# Active_rectifier.net
KiCad netlist of a schematic drawn in EAGLE
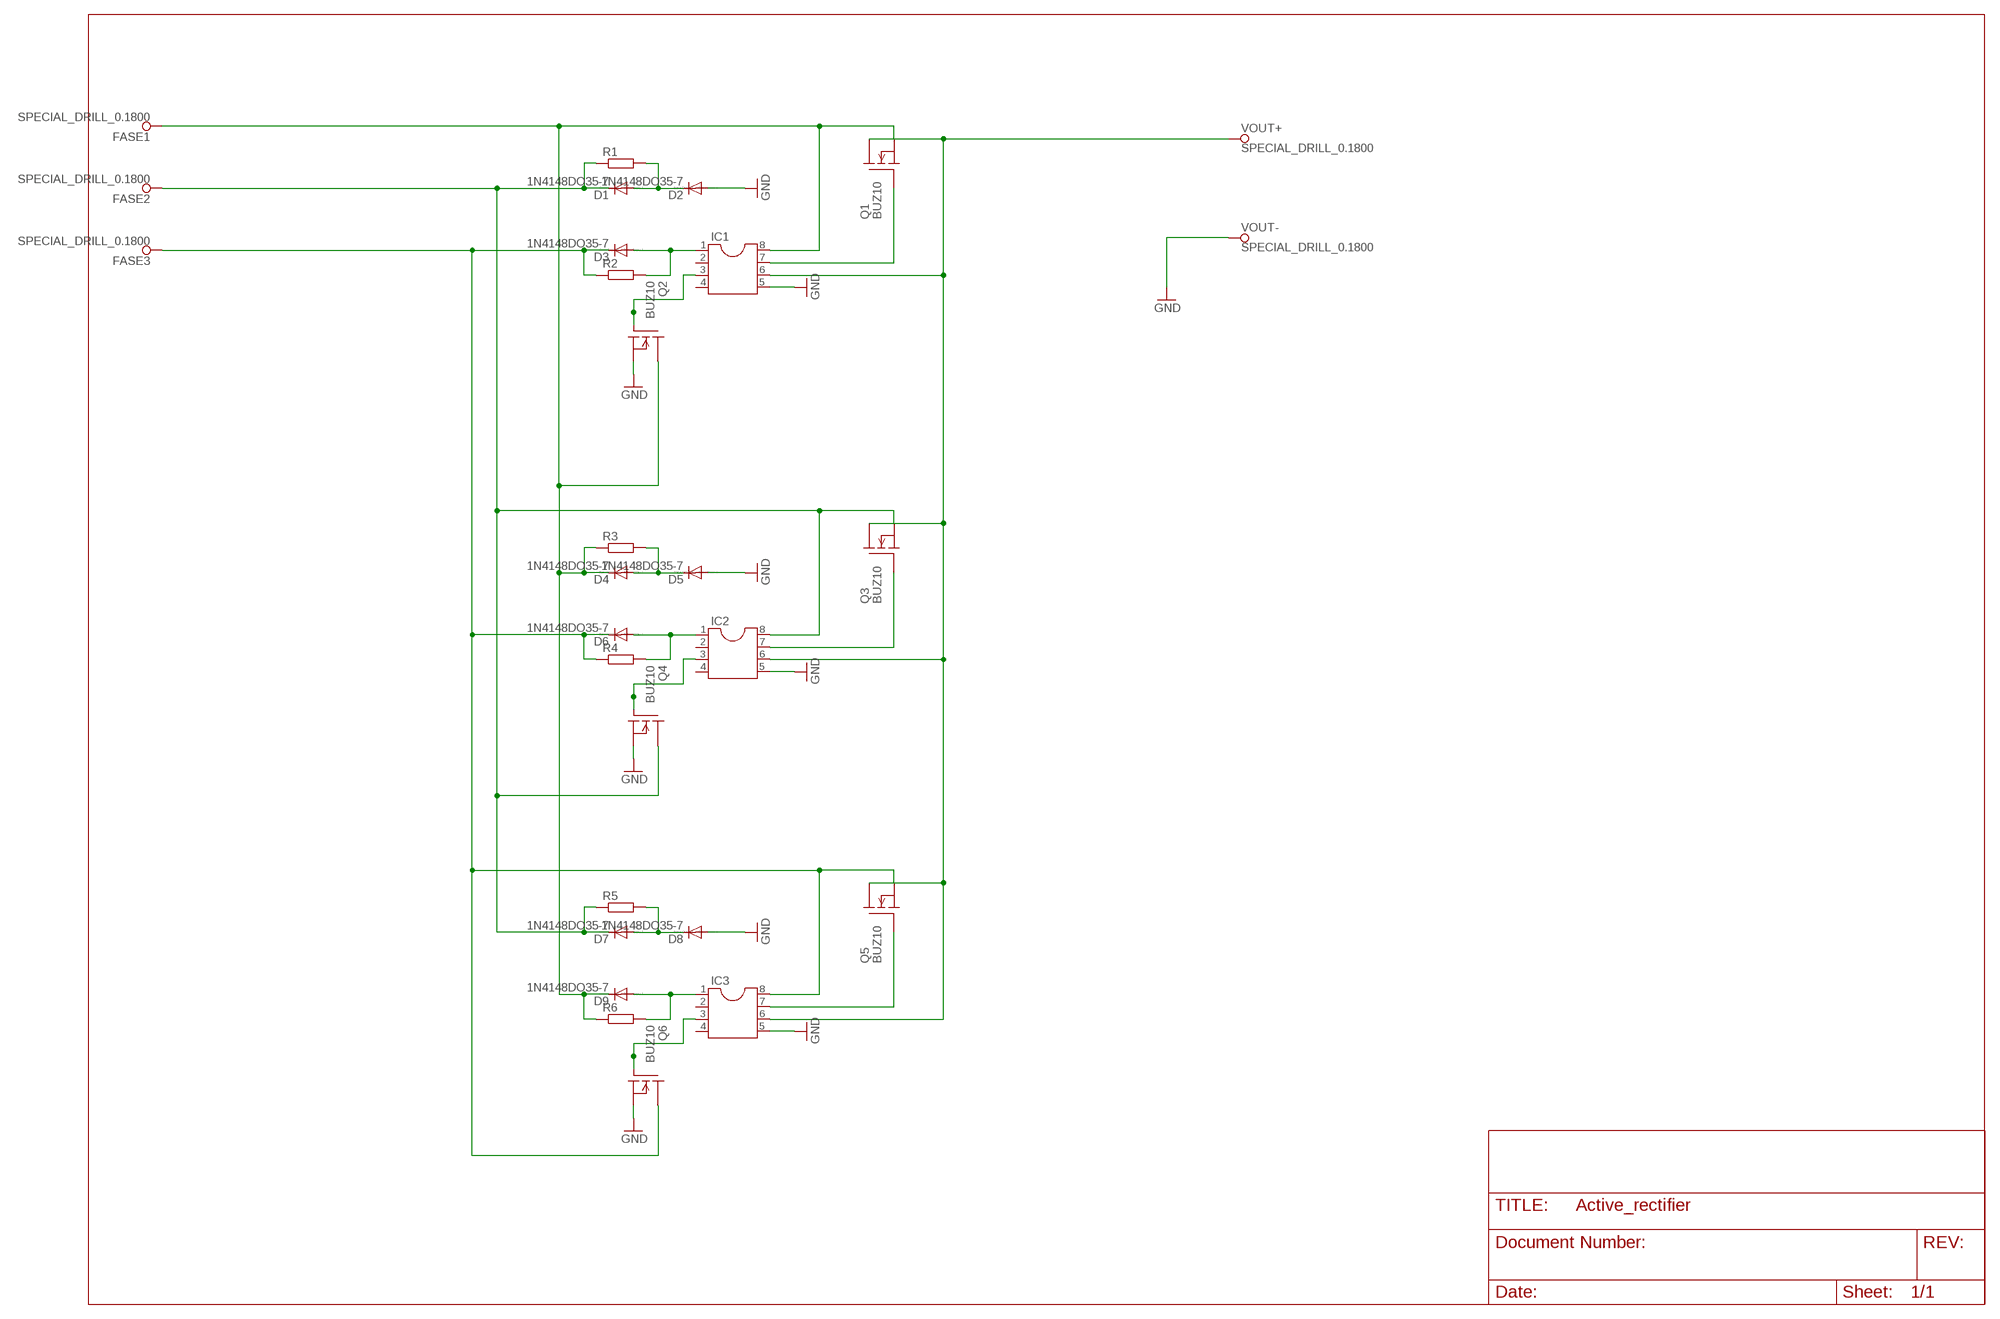
[diagram p0: schematic, sheet 1]

(export (version "E")
  (design (tool "Eeschema 10.0.6"))
  (components
    (comp (ref "D1")
      (value "1N4148DO35-7")
      (footprint "eagle-import:DO35-7")
      (libsource (lib "eagle-import") (part "1N4148DO35-7"))
    )
    (comp (ref "D2")
      (value "1N4148DO35-7")
      (footprint "eagle-import:DO35-7")
      (libsource (lib "eagle-import") (part "1N4148DO35-7"))
    )
    (comp (ref "D3")
      (value "1N4148DO35-7")
      (footprint "eagle-import:DO35-7")
      (libsource (lib "eagle-import") (part "1N4148DO35-7"))
    )
    (comp (ref "D4")
      (value "1N4148DO35-7")
      (footprint "eagle-import:DO35-7")
      (libsource (lib "eagle-import") (part "1N4148DO35-7"))
    )
    (comp (ref "D5")
      (value "1N4148DO35-7")
      (footprint "eagle-import:DO35-7")
      (libsource (lib "eagle-import") (part "1N4148DO35-7"))
    )
    (comp (ref "D6")
      (value "1N4148DO35-7")
      (footprint "eagle-import:DO35-7")
      (libsource (lib "eagle-import") (part "1N4148DO35-7"))
    )
    (comp (ref "D7")
      (value "1N4148DO35-7")
      (footprint "eagle-import:DO35-7")
      (libsource (lib "eagle-import") (part "1N4148DO35-7"))
    )
    (comp (ref "D8")
      (value "1N4148DO35-7")
      (footprint "eagle-import:DO35-7")
      (libsource (lib "eagle-import") (part "1N4148DO35-7"))
    )
    (comp (ref "D9")
      (value "1N4148DO35-7")
      (footprint "eagle-import:DO35-7")
      (libsource (lib "eagle-import") (part "1N4148DO35-7"))
    )
    (comp (ref "FASE1")
      (value "SPECIAL_DRILL_0.1800")
      (footprint "eagle-import:PAD_0.1800")
      (libsource (lib "eagle-import") (part "SPECIAL_DRILL_0.1800"))
    )
    (comp (ref "FASE2")
      (value "SPECIAL_DRILL_0.1800")
      (footprint "eagle-import:PAD_0.1800")
      (libsource (lib "eagle-import") (part "SPECIAL_DRILL_0.1800"))
    )
    (comp (ref "FASE3")
      (value "SPECIAL_DRILL_0.1800")
      (footprint "eagle-import:PAD_0.1800")
      (libsource (lib "eagle-import") (part "SPECIAL_DRILL_0.1800"))
    )
    (comp (ref "IC1")
      (value "DIL8")
      (footprint "eagle-import:DIL08")
      (libsource (lib "eagle-import") (part "DIL8"))
    )
    (comp (ref "IC2")
      (value "DIL8")
      (footprint "eagle-import:DIL08")
      (libsource (lib "eagle-import") (part "DIL8"))
    )
    (comp (ref "IC3")
      (value "DIL8")
      (footprint "eagle-import:DIL08")
      (libsource (lib "eagle-import") (part "DIL8"))
    )
    (comp (ref "Q1")
      (value "BUZ10")
      (footprint "eagle-import:TO220")
      (libsource (lib "eagle-import") (part "BUZ10"))
    )
    (comp (ref "Q2")
      (value "BUZ10")
      (footprint "eagle-import:TO220")
      (libsource (lib "eagle-import") (part "BUZ10"))
    )
    (comp (ref "Q3")
      (value "BUZ10")
      (footprint "eagle-import:TO220")
      (libsource (lib "eagle-import") (part "BUZ10"))
    )
    (comp (ref "Q4")
      (value "BUZ10")
      (footprint "eagle-import:TO220")
      (libsource (lib "eagle-import") (part "BUZ10"))
    )
    (comp (ref "Q5")
      (value "BUZ10")
      (footprint "eagle-import:TO220")
      (libsource (lib "eagle-import") (part "BUZ10"))
    )
    (comp (ref "Q6")
      (value "BUZ10")
      (footprint "eagle-import:TO220")
      (libsource (lib "eagle-import") (part "BUZ10"))
    )
    (comp (ref "R1")
      (value "R-EU_0207/10")
      (footprint "eagle-import:0207_10")
      (libsource (lib "eagle-import") (part "R-EU_0207/10"))
    )
    (comp (ref "R2")
      (value "R-EU_0207/10")
      (footprint "eagle-import:0207_10")
      (libsource (lib "eagle-import") (part "R-EU_0207/10"))
    )
    (comp (ref "R3")
      (value "R-EU_0207/10")
      (footprint "eagle-import:0207_10")
      (libsource (lib "eagle-import") (part "R-EU_0207/10"))
    )
    (comp (ref "R4")
      (value "R-EU_0207/10")
      (footprint "eagle-import:0207_10")
      (libsource (lib "eagle-import") (part "R-EU_0207/10"))
    )
    (comp (ref "R5")
      (value "R-EU_0207/10")
      (footprint "eagle-import:0207_10")
      (libsource (lib "eagle-import") (part "R-EU_0207/10"))
    )
    (comp (ref "R6")
      (value "R-EU_0207/10")
      (footprint "eagle-import:0207_10")
      (libsource (lib "eagle-import") (part "R-EU_0207/10"))
    )
    (comp (ref "VOUT+")
      (value "SPECIAL_DRILL_0.1800")
      (footprint "eagle-import:PAD_0.1800")
      (libsource (lib "eagle-import") (part "SPECIAL_DRILL_0.1800"))
    )
    (comp (ref "VOUT-")
      (value "SPECIAL_DRILL_0.1800")
      (footprint "eagle-import:PAD_0.1800")
      (libsource (lib "eagle-import") (part "SPECIAL_DRILL_0.1800"))
    )
  )
  (nets
    (net (code "1") (name "GND") (class "Default")
      (node (ref "D2") (pin "A") (pinfunction "A_A") (pintype "passive"))
      (node (ref "D5") (pin "A") (pinfunction "A_A") (pintype "passive"))
      (node (ref "D8") (pin "A") (pinfunction "A_A") (pintype "passive"))
      (node (ref "IC1") (pin "5") (pinfunction "5_5") (pintype "passive"))
      (node (ref "IC2") (pin "5") (pinfunction "5_5") (pintype "passive"))
      (node (ref "IC3") (pin "5") (pinfunction "5_5") (pintype "passive"))
      (node (ref "Q2") (pin "3") (pinfunction "S_3") (pintype "passive"))
      (node (ref "Q4") (pin "3") (pinfunction "S_3") (pintype "passive"))
      (node (ref "Q6") (pin "3") (pinfunction "S_3") (pintype "passive"))
      (node (ref "VOUT-") (pin "1") (pinfunction "1_1") (pintype "passive"))
    )
    (net (code "2") (name "Net-(D1-PadA)") (class "Default")
      (node (ref "D1") (pin "A") (pinfunction "A_A") (pintype "passive"))
      (node (ref "D2") (pin "C") (pinfunction "C_C") (pintype "passive"))
      (node (ref "R1") (pin "2") (pinfunction "2_2") (pintype "passive"))
    )
    (net (code "3") (name "Net-(D3-PadA)") (class "Default")
      (node (ref "D3") (pin "A") (pinfunction "A_A") (pintype "passive"))
      (node (ref "IC1") (pin "1") (pinfunction "1_1") (pintype "passive"))
      (node (ref "R2") (pin "2") (pinfunction "2_2") (pintype "passive"))
    )
    (net (code "4") (name "Net-(D4-PadA)") (class "Default")
      (node (ref "D4") (pin "A") (pinfunction "A_A") (pintype "passive"))
      (node (ref "D5") (pin "C") (pinfunction "C_C") (pintype "passive"))
      (node (ref "R3") (pin "2") (pinfunction "2_2") (pintype "passive"))
    )
    (net (code "5") (name "Net-(D6-PadA)") (class "Default")
      (node (ref "D6") (pin "A") (pinfunction "A_A") (pintype "passive"))
      (node (ref "IC2") (pin "1") (pinfunction "1_1") (pintype "passive"))
      (node (ref "R4") (pin "2") (pinfunction "2_2") (pintype "passive"))
    )
    (net (code "6") (name "Net-(D7-PadA)") (class "Default")
      (node (ref "D7") (pin "A") (pinfunction "A_A") (pintype "passive"))
      (node (ref "D8") (pin "C") (pinfunction "C_C") (pintype "passive"))
      (node (ref "R5") (pin "2") (pinfunction "2_2") (pintype "passive"))
    )
    (net (code "7") (name "Net-(D9-PadA)") (class "Default")
      (node (ref "D9") (pin "A") (pinfunction "A_A") (pintype "passive"))
      (node (ref "IC3") (pin "1") (pinfunction "1_1") (pintype "passive"))
      (node (ref "R6") (pin "2") (pinfunction "2_2") (pintype "passive"))
    )
    (net (code "8") (name "Net-(Q1-D)") (class "Default")
      (node (ref "IC1") (pin "6") (pinfunction "6_6") (pintype "passive"))
      (node (ref "IC2") (pin "6") (pinfunction "6_6") (pintype "passive"))
      (node (ref "IC3") (pin "6") (pinfunction "6_6") (pintype "passive"))
      (node (ref "Q1") (pin "2") (pinfunction "D_2") (pintype "passive"))
      (node (ref "Q3") (pin "2") (pinfunction "D_2") (pintype "passive"))
      (node (ref "Q5") (pin "2") (pinfunction "D_2") (pintype "passive"))
      (node (ref "VOUT+") (pin "1") (pinfunction "1_1") (pintype "passive"))
    )
    (net (code "9") (name "Net-(Q1-G)") (class "Default")
      (node (ref "IC1") (pin "7") (pinfunction "7_7") (pintype "passive"))
      (node (ref "Q1") (pin "1") (pinfunction "G_1") (pintype "passive"))
    )
    (net (code "10") (name "Net-(Q1-S)") (class "Default")
      (node (ref "D4") (pin "C") (pinfunction "C_C") (pintype "passive"))
      (node (ref "D9") (pin "C") (pinfunction "C_C") (pintype "passive"))
      (node (ref "FASE1") (pin "1") (pinfunction "1_1") (pintype "passive"))
      (node (ref "IC1") (pin "8") (pinfunction "8_8") (pintype "passive"))
      (node (ref "Q1") (pin "3") (pinfunction "S_3") (pintype "passive"))
      (node (ref "Q2") (pin "2") (pinfunction "D_2") (pintype "passive"))
      (node (ref "R3") (pin "1") (pinfunction "1_1") (pintype "passive"))
      (node (ref "R6") (pin "1") (pinfunction "1_1") (pintype "passive"))
    )
    (net (code "11") (name "Net-(Q2-G)") (class "Default")
      (node (ref "IC1") (pin "3") (pinfunction "3_3") (pintype "passive"))
      (node (ref "Q2") (pin "1") (pinfunction "G_1") (pintype "passive"))
    )
    (net (code "12") (name "Net-(Q3-G)") (class "Default")
      (node (ref "IC2") (pin "7") (pinfunction "7_7") (pintype "passive"))
      (node (ref "Q3") (pin "1") (pinfunction "G_1") (pintype "passive"))
    )
    (net (code "13") (name "Net-(Q3-S)") (class "Default")
      (node (ref "D1") (pin "C") (pinfunction "C_C") (pintype "passive"))
      (node (ref "D7") (pin "C") (pinfunction "C_C") (pintype "passive"))
      (node (ref "FASE2") (pin "1") (pinfunction "1_1") (pintype "passive"))
      (node (ref "IC2") (pin "8") (pinfunction "8_8") (pintype "passive"))
      (node (ref "Q3") (pin "3") (pinfunction "S_3") (pintype "passive"))
      (node (ref "Q4") (pin "2") (pinfunction "D_2") (pintype "passive"))
      (node (ref "R1") (pin "1") (pinfunction "1_1") (pintype "passive"))
      (node (ref "R5") (pin "1") (pinfunction "1_1") (pintype "passive"))
    )
    (net (code "14") (name "Net-(Q4-G)") (class "Default")
      (node (ref "IC2") (pin "3") (pinfunction "3_3") (pintype "passive"))
      (node (ref "Q4") (pin "1") (pinfunction "G_1") (pintype "passive"))
    )
    (net (code "15") (name "Net-(Q5-G)") (class "Default")
      (node (ref "IC3") (pin "7") (pinfunction "7_7") (pintype "passive"))
      (node (ref "Q5") (pin "1") (pinfunction "G_1") (pintype "passive"))
    )
    (net (code "16") (name "Net-(Q5-S)") (class "Default")
      (node (ref "D3") (pin "C") (pinfunction "C_C") (pintype "passive"))
      (node (ref "D6") (pin "C") (pinfunction "C_C") (pintype "passive"))
      (node (ref "FASE3") (pin "1") (pinfunction "1_1") (pintype "passive"))
      (node (ref "IC3") (pin "8") (pinfunction "8_8") (pintype "passive"))
      (node (ref "Q5") (pin "3") (pinfunction "S_3") (pintype "passive"))
      (node (ref "Q6") (pin "2") (pinfunction "D_2") (pintype "passive"))
      (node (ref "R2") (pin "1") (pinfunction "1_1") (pintype "passive"))
      (node (ref "R4") (pin "1") (pinfunction "1_1") (pintype "passive"))
    )
    (net (code "17") (name "Net-(Q6-G)") (class "Default")
      (node (ref "IC3") (pin "3") (pinfunction "3_3") (pintype "passive"))
      (node (ref "Q6") (pin "1") (pinfunction "G_1") (pintype "passive"))
    )
    (net (code "18") (name "unconnected-(IC1-Pad2)") (class "Default")
      (node (ref "IC1") (pin "2") (pinfunction "2_2") (pintype "passive"))
    )
    (net (code "19") (name "unconnected-(IC1-Pad4)") (class "Default")
      (node (ref "IC1") (pin "4") (pinfunction "4_4") (pintype "passive"))
    )
    (net (code "20") (name "unconnected-(IC2-Pad2)") (class "Default")
      (node (ref "IC2") (pin "2") (pinfunction "2_2") (pintype "passive"))
    )
    (net (code "21") (name "unconnected-(IC2-Pad4)") (class "Default")
      (node (ref "IC2") (pin "4") (pinfunction "4_4") (pintype "passive"))
    )
    (net (code "22") (name "unconnected-(IC3-Pad2)") (class "Default")
      (node (ref "IC3") (pin "2") (pinfunction "2_2") (pintype "passive"))
    )
    (net (code "23") (name "unconnected-(IC3-Pad4)") (class "Default")
      (node (ref "IC3") (pin "4") (pinfunction "4_4") (pintype "passive"))
    )
  )
)
